# matrixdriver.net
KiCad netlist of a schematic drawn in EAGLE
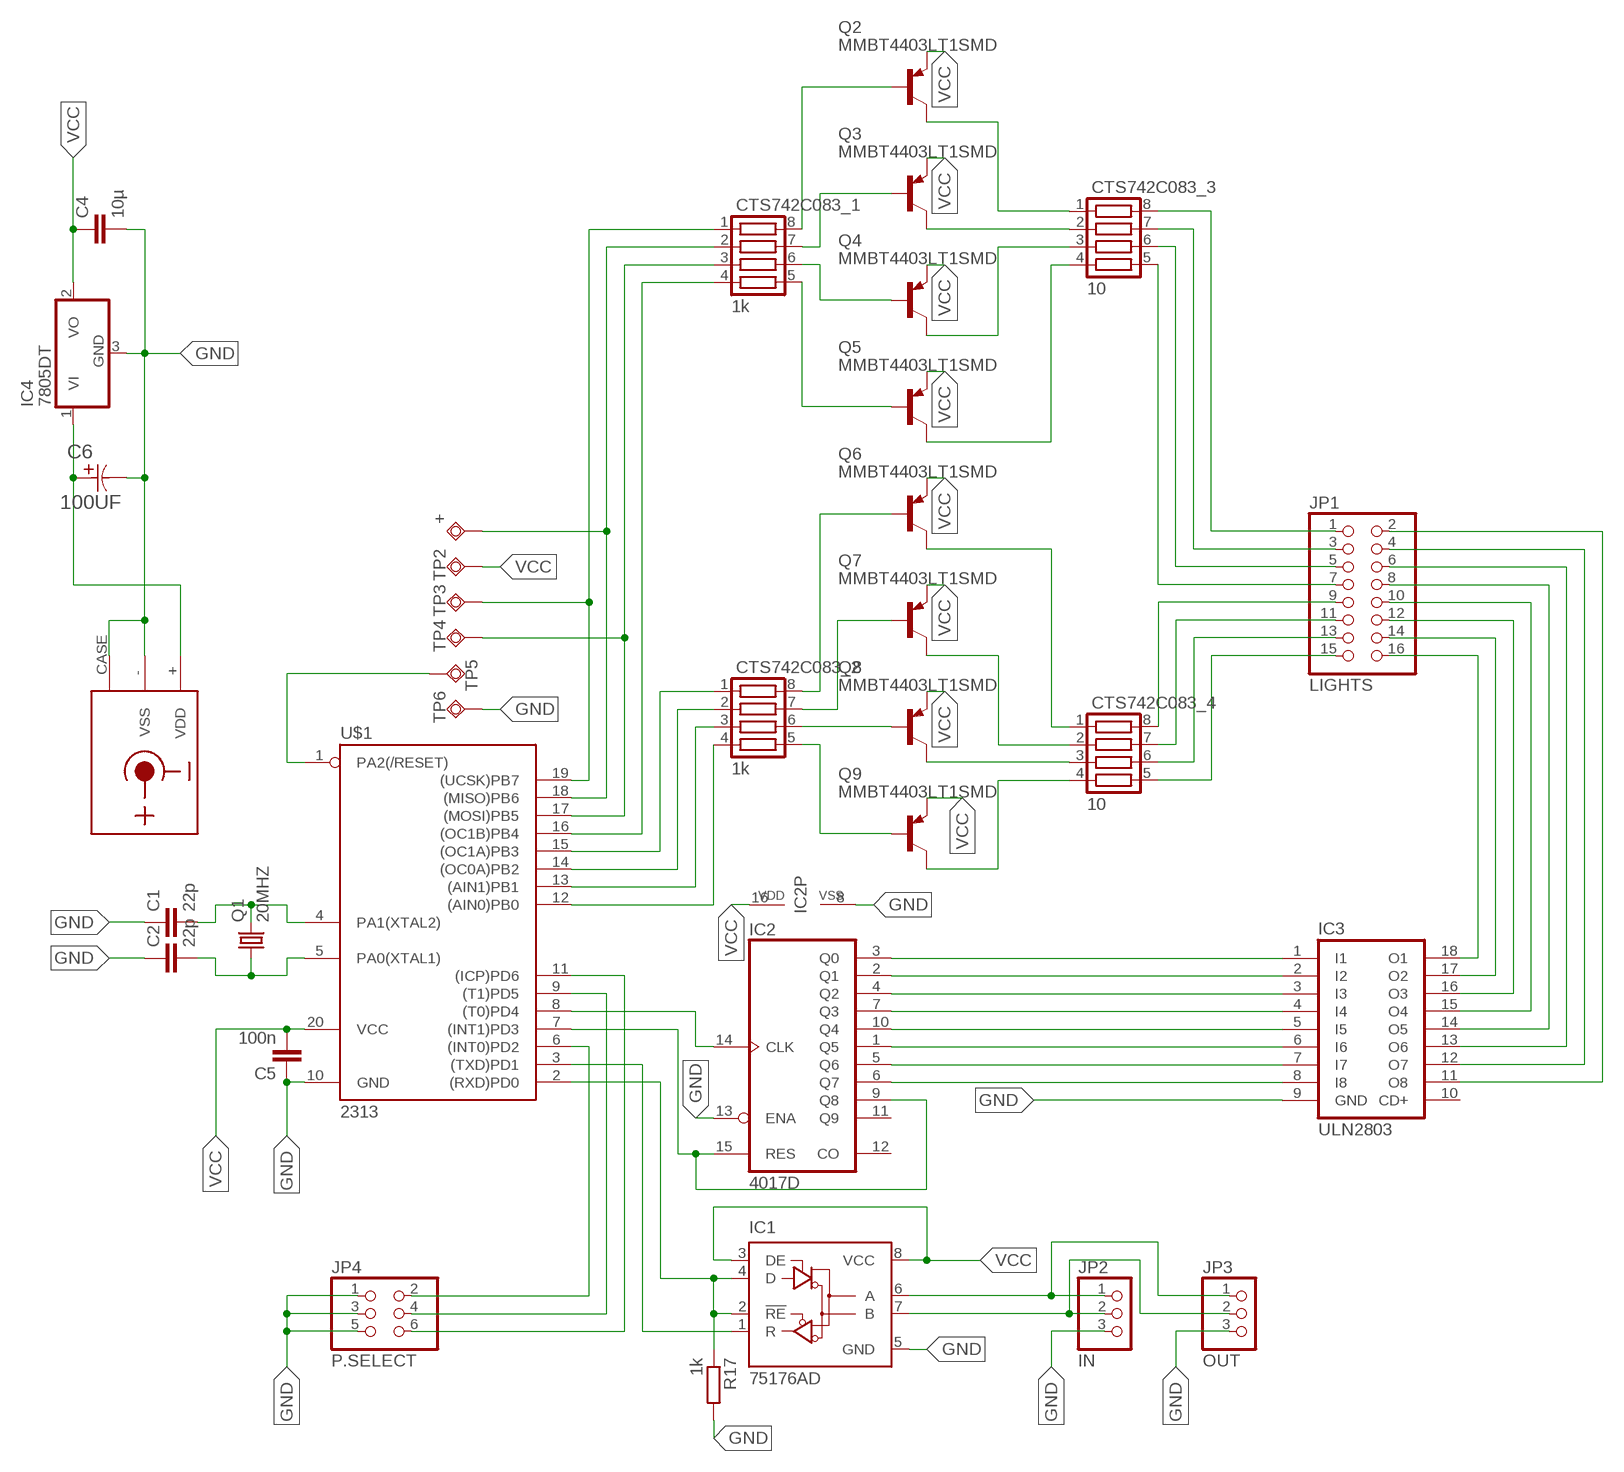
[diagram p0: schematic, sheet 1]

(export (version "E")
  (design (tool "Eeschema 10.0.6"))
  (components
    (comp (ref "+")
      (value "TPSQTP20R")
      (footprint "eagle-import:TP20R")
      (libsource (lib "eagle-import") (part "TPSQTP20R"))
    )
    (comp (ref "C1")
      (value "22p")
      (footprint "eagle-import:C1206")
      (libsource (lib "eagle-import") (part "resistor_C-EUC1206"))
    )
    (comp (ref "C2")
      (value "22p")
      (footprint "eagle-import:C1206")
      (libsource (lib "eagle-import") (part "resistor_C-EUC1206"))
    )
    (comp (ref "C4")
      (value "10µ")
      (footprint "eagle-import:C1206")
      (libsource (lib "eagle-import") (part "C-EUC1206"))
    )
    (comp (ref "C5")
      (value "100n")
      (footprint "eagle-import:C1206")
      (libsource (lib "eagle-import") (part "resistor_C-EUC1206"))
    )
    (comp (ref "C6")
      (value "100UF")
      (footprint "eagle-import:CAPAE660X800N")
      (fields (field (name "MPN") "EEE-HC1C101XP") (field (name "TOLERANCE") "±20 %"))
      (libsource (lib "eagle-import") (part "EEE--CASE-D8HC1C101XP"))
    )
    (comp (ref "CTS742C083_1")
      (value "1k")
      (footprint "eagle-import:CTS742C083")
      (libsource (lib "eagle-import") (part "CTS742C083"))
    )
    (comp (ref "CTS742C083_2")
      (value "1k")
      (footprint "eagle-import:CTS742C083")
      (libsource (lib "eagle-import") (part "CTS742C083"))
    )
    (comp (ref "CTS742C083_3")
      (value "10")
      (footprint "eagle-import:CTS742C083")
      (libsource (lib "eagle-import") (part "CTS742C083"))
    )
    (comp (ref "CTS742C083_4")
      (value "10")
      (footprint "eagle-import:CTS742C083")
      (libsource (lib "eagle-import") (part "CTS742C083"))
    )
    (comp (ref "IC1")
      (value "75176AD")
      (footprint "eagle-import:D_R-PDSO-G8")
      (libsource (lib "eagle-import") (part "75176AD"))
    )
    (comp (ref "IC2")
      (value "4017D")
      (footprint "eagle-import:SO16")
      (libsource (lib "eagle-import") (part "4017D"))
    )
    (comp (ref "IC3")
      (value "ULN2803")
      (footprint "eagle-import:SO18W")
      (libsource (lib "eagle-import") (part "ULN2803ASMD"))
    )
    (comp (ref "IC4")
      (value "7805DT")
      (footprint "eagle-import:TO252")
      (libsource (lib "eagle-import") (part "78DT05"))
    )
    (comp (ref "JP1")
      (value "LIGHTS")
      (footprint "eagle-import:2X08")
      (libsource (lib "eagle-import") (part "PINHD-2X8_2.54"))
    )
    (comp (ref "JP2")
      (value "IN")
      (footprint "eagle-import:1X03")
      (libsource (lib "eagle-import") (part "PINHD-1X3"))
    )
    (comp (ref "JP3")
      (value "OUT")
      (footprint "eagle-import:1X03")
      (libsource (lib "eagle-import") (part "PINHD-1X3"))
    )
    (comp (ref "JP4")
      (value "P.SELECT")
      (footprint "eagle-import:2X03")
      (libsource (lib "eagle-import") (part "PINHD-2X3"))
    )
    (comp (ref "Q1")
      (value "20MHZ")
      (footprint "eagle-import:HC49UP")
      (libsource (lib "eagle-import") (part "CRYSTALHC49UP"))
    )
    (comp (ref "Q2")
      (value "MMBT4403LT1SMD")
      (footprint "eagle-import:SOT23-BEC")
      (libsource (lib "eagle-import") (part "MMBT4403SMDLT1"))
    )
    (comp (ref "Q3")
      (value "MMBT4403LT1SMD")
      (footprint "eagle-import:SOT23-BEC")
      (libsource (lib "eagle-import") (part "MMBT4403SMDLT1"))
    )
    (comp (ref "Q4")
      (value "MMBT4403LT1SMD")
      (footprint "eagle-import:SOT23-BEC")
      (libsource (lib "eagle-import") (part "MMBT4403SMDLT1"))
    )
    (comp (ref "Q5")
      (value "MMBT4403LT1SMD")
      (footprint "eagle-import:SOT23-BEC")
      (libsource (lib "eagle-import") (part "MMBT4403SMDLT1"))
    )
    (comp (ref "Q6")
      (value "MMBT4403LT1SMD")
      (footprint "eagle-import:SOT23-BEC")
      (libsource (lib "eagle-import") (part "MMBT4403SMDLT1"))
    )
    (comp (ref "Q7")
      (value "MMBT4403LT1SMD")
      (footprint "eagle-import:SOT23-BEC")
      (libsource (lib "eagle-import") (part "MMBT4403SMDLT1"))
    )
    (comp (ref "Q8")
      (value "MMBT4403LT1SMD")
      (footprint "eagle-import:SOT23-BEC")
      (libsource (lib "eagle-import") (part "MMBT4403SMDLT1"))
    )
    (comp (ref "Q9")
      (value "MMBT4403LT1SMD")
      (footprint "eagle-import:SOT23-BEC")
      (libsource (lib "eagle-import") (part "MMBT4403SMDLT1"))
    )
    (comp (ref "R17")
      (value "1k")
      (footprint "eagle-import:R1206")
      (libsource (lib "eagle-import") (part "R-EU_R1206"))
    )
    (comp (ref "TP2")
      (value "TPSQTP19SQ")
      (footprint "eagle-import:TP19SQ")
      (libsource (lib "eagle-import") (part "TPSQTP19SQ"))
    )
    (comp (ref "TP3")
      (value "TPSQTP20SQ")
      (footprint "eagle-import:TP20SQ")
      (libsource (lib "eagle-import") (part "TPSQTP20SQ"))
    )
    (comp (ref "TP4")
      (value "TPSQTP20SQ")
      (footprint "eagle-import:TP20SQ")
      (libsource (lib "eagle-import") (part "TPSQTP20SQ"))
    )
    (comp (ref "TP5")
      (value "TPSQTP20SQ")
      (footprint "eagle-import:TP20SQ")
      (libsource (lib "eagle-import") (part "TPSQTP20SQ"))
    )
    (comp (ref "TP6")
      (value "TPSQTP20SQ")
      (footprint "eagle-import:TP20SQ")
      (libsource (lib "eagle-import") (part "TPSQTP20SQ"))
    )
    (comp (ref "U$1")
      (value "2313")
      (footprint "eagle-import:SO20L$")
      (libsource (lib "eagle-import") (part "TINY2313-S"))
    )
    (comp (ref "U$2")
      (value "CUI_PJ-102A")
      (footprint "eagle-import:CUI_DCJACK_PCB")
      (libsource (lib "eagle-import") (part "CUI_PJ-102A"))
    )
  )
  (nets
    (net (code "1") (name "GND") (class "Default")
      (node (ref "C1") (pin "1") (pinfunction "1_1") (pintype "passive"))
      (node (ref "C2") (pin "1") (pinfunction "1_1") (pintype "passive"))
      (node (ref "C4") (pin "2") (pinfunction "2_2") (pintype "passive"))
      (node (ref "C5") (pin "1") (pinfunction "1_1") (pintype "passive"))
      (node (ref "C6") (pin "2") (pinfunction "2_2") (pintype "passive"))
      (node (ref "IC1") (pin "5") (pinfunction "GND_5") (pintype "power_in"))
      (node (ref "IC2") (pin "13") (pinfunction "ENA_13") (pintype "input"))
      (node (ref "IC2") (pin "8") (pinfunction "VSS_8") (pintype "power_in"))
      (node (ref "IC3") (pin "9") (pinfunction "GND_9") (pintype "power_in"))
      (node (ref "IC4") (pin "3") (pinfunction "GND_3") (pintype "passive"))
      (node (ref "JP2") (pin "3") (pinfunction "3_3") (pintype "passive"))
      (node (ref "JP3") (pin "3") (pinfunction "3_3") (pintype "passive"))
      (node (ref "JP4") (pin "1") (pinfunction "1_1") (pintype "passive"))
      (node (ref "JP4") (pin "3") (pinfunction "3_3") (pintype "passive"))
      (node (ref "JP4") (pin "5") (pinfunction "5_5") (pintype "passive"))
      (node (ref "R17") (pin "2") (pinfunction "2_2") (pintype "passive"))
      (node (ref "TP6") (pin "TP") (pinfunction "TP_TP") (pintype "input"))
      (node (ref "U$1") (pin "10") (pinfunction "GND_10") (pintype "power_in"))
      (node (ref "U$2") (pin "-") (pinfunction "VSS_-") (pintype "power_in"))
      (node (ref "U$2") (pin "CASE") (pintype "power_in"))
    )
    (net (code "2") (name "Net-(CTS742C083_1-Pad5)") (class "Default")
      (node (ref "CTS742C083_1") (pin "5") (pinfunction "5_5") (pintype "passive"))
      (node (ref "Q5") (pin "B") (pinfunction "B_B") (pintype "passive"))
    )
    (net (code "3") (name "Net-(CTS742C083_1-Pad6)") (class "Default")
      (node (ref "CTS742C083_1") (pin "6") (pinfunction "6_6") (pintype "passive"))
      (node (ref "Q4") (pin "B") (pinfunction "B_B") (pintype "passive"))
    )
    (net (code "4") (name "Net-(CTS742C083_1-Pad7)") (class "Default")
      (node (ref "CTS742C083_1") (pin "7") (pinfunction "7_7") (pintype "passive"))
      (node (ref "Q3") (pin "B") (pinfunction "B_B") (pintype "passive"))
    )
    (net (code "5") (name "Net-(CTS742C083_1-Pad8)") (class "Default")
      (node (ref "CTS742C083_1") (pin "8") (pinfunction "8_8") (pintype "passive"))
      (node (ref "Q2") (pin "B") (pinfunction "B_B") (pintype "passive"))
    )
    (net (code "6") (name "Net-(CTS742C083_2-Pad5)") (class "Default")
      (node (ref "CTS742C083_2") (pin "5") (pinfunction "5_5") (pintype "passive"))
      (node (ref "Q9") (pin "B") (pinfunction "B_B") (pintype "passive"))
    )
    (net (code "7") (name "Net-(CTS742C083_2-Pad6)") (class "Default")
      (node (ref "CTS742C083_2") (pin "6") (pinfunction "6_6") (pintype "passive"))
      (node (ref "Q8") (pin "B") (pinfunction "B_B") (pintype "passive"))
    )
    (net (code "8") (name "Net-(CTS742C083_2-Pad7)") (class "Default")
      (node (ref "CTS742C083_2") (pin "7") (pinfunction "7_7") (pintype "passive"))
      (node (ref "Q7") (pin "B") (pinfunction "B_B") (pintype "passive"))
    )
    (net (code "9") (name "Net-(CTS742C083_2-Pad8)") (class "Default")
      (node (ref "CTS742C083_2") (pin "8") (pinfunction "8_8") (pintype "passive"))
      (node (ref "Q6") (pin "B") (pinfunction "B_B") (pintype "passive"))
    )
    (net (code "10") (name "Net-(CTS742C083_3-Pad1)") (class "Default")
      (node (ref "CTS742C083_3") (pin "1") (pinfunction "1_1") (pintype "passive"))
      (node (ref "Q2") (pin "C") (pinfunction "C_C") (pintype "passive"))
    )
    (net (code "11") (name "Net-(CTS742C083_3-Pad2)") (class "Default")
      (node (ref "CTS742C083_3") (pin "2") (pinfunction "2_2") (pintype "passive"))
      (node (ref "Q3") (pin "C") (pinfunction "C_C") (pintype "passive"))
    )
    (net (code "12") (name "Net-(CTS742C083_3-Pad3)") (class "Default")
      (node (ref "CTS742C083_3") (pin "3") (pinfunction "3_3") (pintype "passive"))
      (node (ref "Q4") (pin "C") (pinfunction "C_C") (pintype "passive"))
    )
    (net (code "13") (name "Net-(CTS742C083_3-Pad4)") (class "Default")
      (node (ref "CTS742C083_3") (pin "4") (pinfunction "4_4") (pintype "passive"))
      (node (ref "Q5") (pin "C") (pinfunction "C_C") (pintype "passive"))
    )
    (net (code "14") (name "Net-(CTS742C083_3-Pad5)") (class "Default")
      (node (ref "CTS742C083_3") (pin "5") (pinfunction "5_5") (pintype "passive"))
      (node (ref "JP1") (pin "7") (pinfunction "7_7") (pintype "passive"))
    )
    (net (code "15") (name "Net-(CTS742C083_3-Pad6)") (class "Default")
      (node (ref "CTS742C083_3") (pin "6") (pinfunction "6_6") (pintype "passive"))
      (node (ref "JP1") (pin "5") (pinfunction "5_5") (pintype "passive"))
    )
    (net (code "16") (name "Net-(CTS742C083_3-Pad7)") (class "Default")
      (node (ref "CTS742C083_3") (pin "7") (pinfunction "7_7") (pintype "passive"))
      (node (ref "JP1") (pin "3") (pinfunction "3_3") (pintype "passive"))
    )
    (net (code "17") (name "Net-(CTS742C083_3-Pad8)") (class "Default")
      (node (ref "CTS742C083_3") (pin "8") (pinfunction "8_8") (pintype "passive"))
      (node (ref "JP1") (pin "1") (pinfunction "1_1") (pintype "passive"))
    )
    (net (code "18") (name "Net-(CTS742C083_4-Pad1)") (class "Default")
      (node (ref "CTS742C083_4") (pin "1") (pinfunction "1_1") (pintype "passive"))
      (node (ref "Q6") (pin "C") (pinfunction "C_C") (pintype "passive"))
    )
    (net (code "19") (name "Net-(CTS742C083_4-Pad2)") (class "Default")
      (node (ref "CTS742C083_4") (pin "2") (pinfunction "2_2") (pintype "passive"))
      (node (ref "Q7") (pin "C") (pinfunction "C_C") (pintype "passive"))
    )
    (net (code "20") (name "Net-(CTS742C083_4-Pad3)") (class "Default")
      (node (ref "CTS742C083_4") (pin "3") (pinfunction "3_3") (pintype "passive"))
      (node (ref "Q8") (pin "C") (pinfunction "C_C") (pintype "passive"))
    )
    (net (code "21") (name "Net-(CTS742C083_4-Pad4)") (class "Default")
      (node (ref "CTS742C083_4") (pin "4") (pinfunction "4_4") (pintype "passive"))
      (node (ref "Q9") (pin "C") (pinfunction "C_C") (pintype "passive"))
    )
    (net (code "22") (name "Net-(CTS742C083_4-Pad5)") (class "Default")
      (node (ref "CTS742C083_4") (pin "5") (pinfunction "5_5") (pintype "passive"))
      (node (ref "JP1") (pin "15") (pinfunction "15_15") (pintype "passive"))
    )
    (net (code "23") (name "Net-(CTS742C083_4-Pad6)") (class "Default")
      (node (ref "CTS742C083_4") (pin "6") (pinfunction "6_6") (pintype "passive"))
      (node (ref "JP1") (pin "13") (pinfunction "13_13") (pintype "passive"))
    )
    (net (code "24") (name "Net-(CTS742C083_4-Pad7)") (class "Default")
      (node (ref "CTS742C083_4") (pin "7") (pinfunction "7_7") (pintype "passive"))
      (node (ref "JP1") (pin "11") (pinfunction "11_11") (pintype "passive"))
    )
    (net (code "25") (name "Net-(CTS742C083_4-Pad8)") (class "Default")
      (node (ref "CTS742C083_4") (pin "8") (pinfunction "8_8") (pintype "passive"))
      (node (ref "JP1") (pin "9") (pinfunction "9_9") (pintype "passive"))
    )
    (net (code "26") (name "Net-(IC1-A)") (class "Default")
      (node (ref "IC1") (pin "6") (pinfunction "A_6") (pintype "output"))
      (node (ref "JP2") (pin "1") (pinfunction "1_1") (pintype "passive"))
      (node (ref "JP3") (pin "1") (pinfunction "1_1") (pintype "passive"))
    )
    (net (code "27") (name "Net-(IC1-B)") (class "Default")
      (node (ref "IC1") (pin "7") (pinfunction "B_7") (pintype "output"))
      (node (ref "JP2") (pin "2") (pinfunction "2_2") (pintype "passive"))
      (node (ref "JP3") (pin "2") (pinfunction "2_2") (pintype "passive"))
    )
    (net (code "28") (name "Net-(IC1-D)") (class "Default")
      (node (ref "IC1") (pin "2") (pinfunction "~{RE}_2") (pintype "input"))
      (node (ref "IC1") (pin "4") (pinfunction "D_4") (pintype "input"))
      (node (ref "R17") (pin "1") (pinfunction "1_1") (pintype "passive"))
      (node (ref "U$1") (pin "2") (pinfunction "(RXD)PD0_2") (pintype "bidirectional"))
    )
    (net (code "29") (name "Net-(IC1-R)") (class "Default")
      (node (ref "IC1") (pin "1") (pinfunction "R_1") (pintype "input"))
      (node (ref "U$1") (pin "3") (pinfunction "(TXD)PD1_3") (pintype "bidirectional"))
    )
    (net (code "30") (name "Net-(IC2A-CLK)") (class "Default")
      (node (ref "IC2") (pin "14") (pinfunction "CLK_14") (pintype "input"))
      (node (ref "U$1") (pin "8") (pinfunction "(T0)PD4_8") (pintype "bidirectional"))
    )
    (net (code "31") (name "Net-(IC2A-Q0)") (class "Default")
      (node (ref "IC2") (pin "3") (pinfunction "Q0_3") (pintype "output"))
      (node (ref "IC3") (pin "1") (pinfunction "I1_1") (pintype "input"))
    )
    (net (code "32") (name "Net-(IC2A-Q1)") (class "Default")
      (node (ref "IC2") (pin "2") (pinfunction "Q1_2") (pintype "output"))
      (node (ref "IC3") (pin "2") (pinfunction "I2_2") (pintype "input"))
    )
    (net (code "33") (name "Net-(IC2A-Q2)") (class "Default")
      (node (ref "IC2") (pin "4") (pinfunction "Q2_4") (pintype "output"))
      (node (ref "IC3") (pin "3") (pinfunction "I3_3") (pintype "input"))
    )
    (net (code "34") (name "Net-(IC2A-Q3)") (class "Default")
      (node (ref "IC2") (pin "7") (pinfunction "Q3_7") (pintype "output"))
      (node (ref "IC3") (pin "4") (pinfunction "I4_4") (pintype "input"))
    )
    (net (code "35") (name "Net-(IC2A-Q4)") (class "Default")
      (node (ref "IC2") (pin "10") (pinfunction "Q4_10") (pintype "output"))
      (node (ref "IC3") (pin "5") (pinfunction "I5_5") (pintype "input"))
    )
    (net (code "36") (name "Net-(IC2A-Q5)") (class "Default")
      (node (ref "IC2") (pin "1") (pinfunction "Q5_1") (pintype "output"))
      (node (ref "IC3") (pin "6") (pinfunction "I6_6") (pintype "input"))
    )
    (net (code "37") (name "Net-(IC2A-Q6)") (class "Default")
      (node (ref "IC2") (pin "5") (pinfunction "Q6_5") (pintype "output"))
      (node (ref "IC3") (pin "7") (pinfunction "I7_7") (pintype "input"))
    )
    (net (code "38") (name "Net-(IC2A-Q7)") (class "Default")
      (node (ref "IC2") (pin "6") (pinfunction "Q7_6") (pintype "output"))
      (node (ref "IC3") (pin "8") (pinfunction "I8_8") (pintype "input"))
    )
    (net (code "39") (name "Net-(IC2A-Q8)") (class "Default")
      (node (ref "IC2") (pin "15") (pinfunction "RES_15") (pintype "input"))
      (node (ref "IC2") (pin "9") (pinfunction "Q8_9") (pintype "output"))
      (node (ref "U$1") (pin "7") (pinfunction "(INT1)PD3_7") (pintype "bidirectional"))
    )
    (net (code "40") (name "Net-(IC3-O1)") (class "Default")
      (node (ref "IC3") (pin "18") (pinfunction "O1_18") (pintype "open_collector"))
      (node (ref "JP1") (pin "16") (pinfunction "16_16") (pintype "passive"))
    )
    (net (code "41") (name "Net-(IC3-O2)") (class "Default")
      (node (ref "IC3") (pin "17") (pinfunction "O2_17") (pintype "open_collector"))
      (node (ref "JP1") (pin "14") (pinfunction "14_14") (pintype "passive"))
    )
    (net (code "42") (name "Net-(IC3-O3)") (class "Default")
      (node (ref "IC3") (pin "16") (pinfunction "O3_16") (pintype "open_collector"))
      (node (ref "JP1") (pin "12") (pinfunction "12_12") (pintype "passive"))
    )
    (net (code "43") (name "Net-(IC3-O4)") (class "Default")
      (node (ref "IC3") (pin "15") (pinfunction "O4_15") (pintype "open_collector"))
      (node (ref "JP1") (pin "10") (pinfunction "10_10") (pintype "passive"))
    )
    (net (code "44") (name "Net-(IC3-O5)") (class "Default")
      (node (ref "IC3") (pin "14") (pinfunction "O5_14") (pintype "open_collector"))
      (node (ref "JP1") (pin "8") (pinfunction "8_8") (pintype "passive"))
    )
    (net (code "45") (name "Net-(IC3-O6)") (class "Default")
      (node (ref "IC3") (pin "13") (pinfunction "O6_13") (pintype "open_collector"))
      (node (ref "JP1") (pin "6") (pinfunction "6_6") (pintype "passive"))
    )
    (net (code "46") (name "Net-(IC3-O7)") (class "Default")
      (node (ref "IC3") (pin "12") (pinfunction "O7_12") (pintype "open_collector"))
      (node (ref "JP1") (pin "4") (pinfunction "4_4") (pintype "passive"))
    )
    (net (code "47") (name "Net-(IC3-O8)") (class "Default")
      (node (ref "IC3") (pin "11") (pinfunction "O8_11") (pintype "open_collector"))
      (node (ref "JP1") (pin "2") (pinfunction "2_2") (pintype "passive"))
    )
    (net (code "48") (name "Net-(IC4-VI)") (class "Default")
      (node (ref "C6") (pin "1") (pinfunction "1_1") (pintype "passive"))
      (node (ref "IC4") (pin "1") (pinfunction "VI_1") (pintype "input"))
      (node (ref "U$2") (pin "+") (pinfunction "VDD_+") (pintype "power_in"))
    )
    (net (code "49") (name "Net-(U$1-(AIN0)PB0)") (class "Default")
      (node (ref "CTS742C083_2") (pin "4") (pinfunction "4_4") (pintype "passive"))
      (node (ref "U$1") (pin "12") (pinfunction "(AIN0)PB0_12") (pintype "bidirectional"))
    )
    (net (code "50") (name "Net-(U$1-(AIN1)PB1)") (class "Default")
      (node (ref "CTS742C083_2") (pin "3") (pinfunction "3_3") (pintype "passive"))
      (node (ref "U$1") (pin "13") (pinfunction "(AIN1)PB1_13") (pintype "bidirectional"))
    )
    (net (code "51") (name "Net-(U$1-(ICP)PD6)") (class "Default")
      (node (ref "JP4") (pin "6") (pinfunction "6_6") (pintype "passive"))
      (node (ref "U$1") (pin "11") (pinfunction "(ICP)PD6_11") (pintype "bidirectional"))
    )
    (net (code "52") (name "Net-(U$1-(INT0)PD2)") (class "Default")
      (node (ref "JP4") (pin "2") (pinfunction "2_2") (pintype "passive"))
      (node (ref "U$1") (pin "6") (pinfunction "(INT0)PD2_6") (pintype "bidirectional"))
    )
    (net (code "53") (name "Net-(U$1-(MISO)PB6)") (class "Default")
      (node (ref "+") (pin "TP") (pinfunction "TP_TP") (pintype "input"))
      (node (ref "CTS742C083_1") (pin "2") (pinfunction "2_2") (pintype "passive"))
      (node (ref "U$1") (pin "18") (pinfunction "(MISO)PB6_18") (pintype "bidirectional"))
    )
    (net (code "54") (name "Net-(U$1-(MOSI)PB5)") (class "Default")
      (node (ref "CTS742C083_1") (pin "3") (pinfunction "3_3") (pintype "passive"))
      (node (ref "TP4") (pin "TP") (pinfunction "TP_TP") (pintype "input"))
      (node (ref "U$1") (pin "17") (pinfunction "(MOSI)PB5_17") (pintype "bidirectional"))
    )
    (net (code "55") (name "Net-(U$1-(OC0A)PB2)") (class "Default")
      (node (ref "CTS742C083_2") (pin "2") (pinfunction "2_2") (pintype "passive"))
      (node (ref "U$1") (pin "14") (pinfunction "(OC0A)PB2_14") (pintype "bidirectional"))
    )
    (net (code "56") (name "Net-(U$1-(OC1A)PB3)") (class "Default")
      (node (ref "CTS742C083_2") (pin "1") (pinfunction "1_1") (pintype "passive"))
      (node (ref "U$1") (pin "15") (pinfunction "(OC1A)PB3_15") (pintype "bidirectional"))
    )
    (net (code "57") (name "Net-(U$1-(OC1B)PB4)") (class "Default")
      (node (ref "CTS742C083_1") (pin "4") (pinfunction "4_4") (pintype "passive"))
      (node (ref "U$1") (pin "16") (pinfunction "(OC1B)PB4_16") (pintype "bidirectional"))
    )
    (net (code "58") (name "Net-(U$1-(T1)PD5)") (class "Default")
      (node (ref "JP4") (pin "4") (pinfunction "4_4") (pintype "passive"))
      (node (ref "U$1") (pin "9") (pinfunction "(T1)PD5_9") (pintype "bidirectional"))
    )
    (net (code "59") (name "Net-(U$1-(UCSK)PB7)") (class "Default")
      (node (ref "CTS742C083_1") (pin "1") (pinfunction "1_1") (pintype "passive"))
      (node (ref "TP3") (pin "TP") (pinfunction "TP_TP") (pintype "input"))
      (node (ref "U$1") (pin "19") (pinfunction "(UCSK)PB7_19") (pintype "bidirectional"))
    )
    (net (code "60") (name "Net-(U$1-PA0(XTAL1))") (class "Default")
      (node (ref "C2") (pin "2") (pinfunction "2_2") (pintype "passive"))
      (node (ref "Q1") (pin "1") (pinfunction "1_1") (pintype "passive"))
      (node (ref "U$1") (pin "5") (pinfunction "PA0(XTAL1)_5") (pintype "bidirectional"))
    )
    (net (code "61") (name "Net-(U$1-PA1(XTAL2))") (class "Default")
      (node (ref "C1") (pin "2") (pinfunction "2_2") (pintype "passive"))
      (node (ref "Q1") (pin "2") (pinfunction "2_2") (pintype "passive"))
      (node (ref "U$1") (pin "4") (pinfunction "PA1(XTAL2)_4") (pintype "bidirectional"))
    )
    (net (code "62") (name "Net-(U$1-PA2({slash}RESET))") (class "Default")
      (node (ref "TP5") (pin "TP") (pinfunction "TP_TP") (pintype "input"))
      (node (ref "U$1") (pin "1") (pinfunction "PA2(/RESET)_1") (pintype "input"))
    )
    (net (code "63") (name "VCC") (class "Default")
      (node (ref "C4") (pin "1") (pinfunction "1_1") (pintype "passive"))
      (node (ref "C5") (pin "2") (pinfunction "2_2") (pintype "passive"))
      (node (ref "IC1") (pin "3") (pinfunction "DE_3") (pintype "input"))
      (node (ref "IC1") (pin "8") (pinfunction "VCC_8") (pintype "power_in"))
      (node (ref "IC2") (pin "16") (pinfunction "VDD_16") (pintype "power_in"))
      (node (ref "IC4") (pin "2") (pinfunction "VO_2") (pintype "passive"))
      (node (ref "Q2") (pin "E") (pinfunction "E_E") (pintype "passive"))
      (node (ref "Q3") (pin "E") (pinfunction "E_E") (pintype "passive"))
      (node (ref "Q4") (pin "E") (pinfunction "E_E") (pintype "passive"))
      (node (ref "Q5") (pin "E") (pinfunction "E_E") (pintype "passive"))
      (node (ref "Q6") (pin "E") (pinfunction "E_E") (pintype "passive"))
      (node (ref "Q7") (pin "E") (pinfunction "E_E") (pintype "passive"))
      (node (ref "Q8") (pin "E") (pinfunction "E_E") (pintype "passive"))
      (node (ref "Q9") (pin "E") (pinfunction "E_E") (pintype "passive"))
      (node (ref "TP2") (pin "TP") (pinfunction "TP_TP") (pintype "input"))
      (node (ref "U$1") (pin "20") (pinfunction "VCC_20") (pintype "power_in"))
    )
    (net (code "64") (name "unconnected-(IC2A-CO-Pad12)") (class "Default")
      (node (ref "IC2") (pin "12") (pinfunction "CO_12") (pintype "output"))
    )
    (net (code "65") (name "unconnected-(IC2A-Q9-Pad11)") (class "Default")
      (node (ref "IC2") (pin "11") (pinfunction "Q9_11") (pintype "output"))
    )
    (net (code "66") (name "unconnected-(IC3-CD+-Pad10)") (class "Default")
      (node (ref "IC3") (pin "10") (pinfunction "CD+_10") (pintype "passive"))
    )
  )
)
